# 02_SPEAKER_LED_STRIPS.net
KiCad netlist of a schematic drawn in Altium Designer
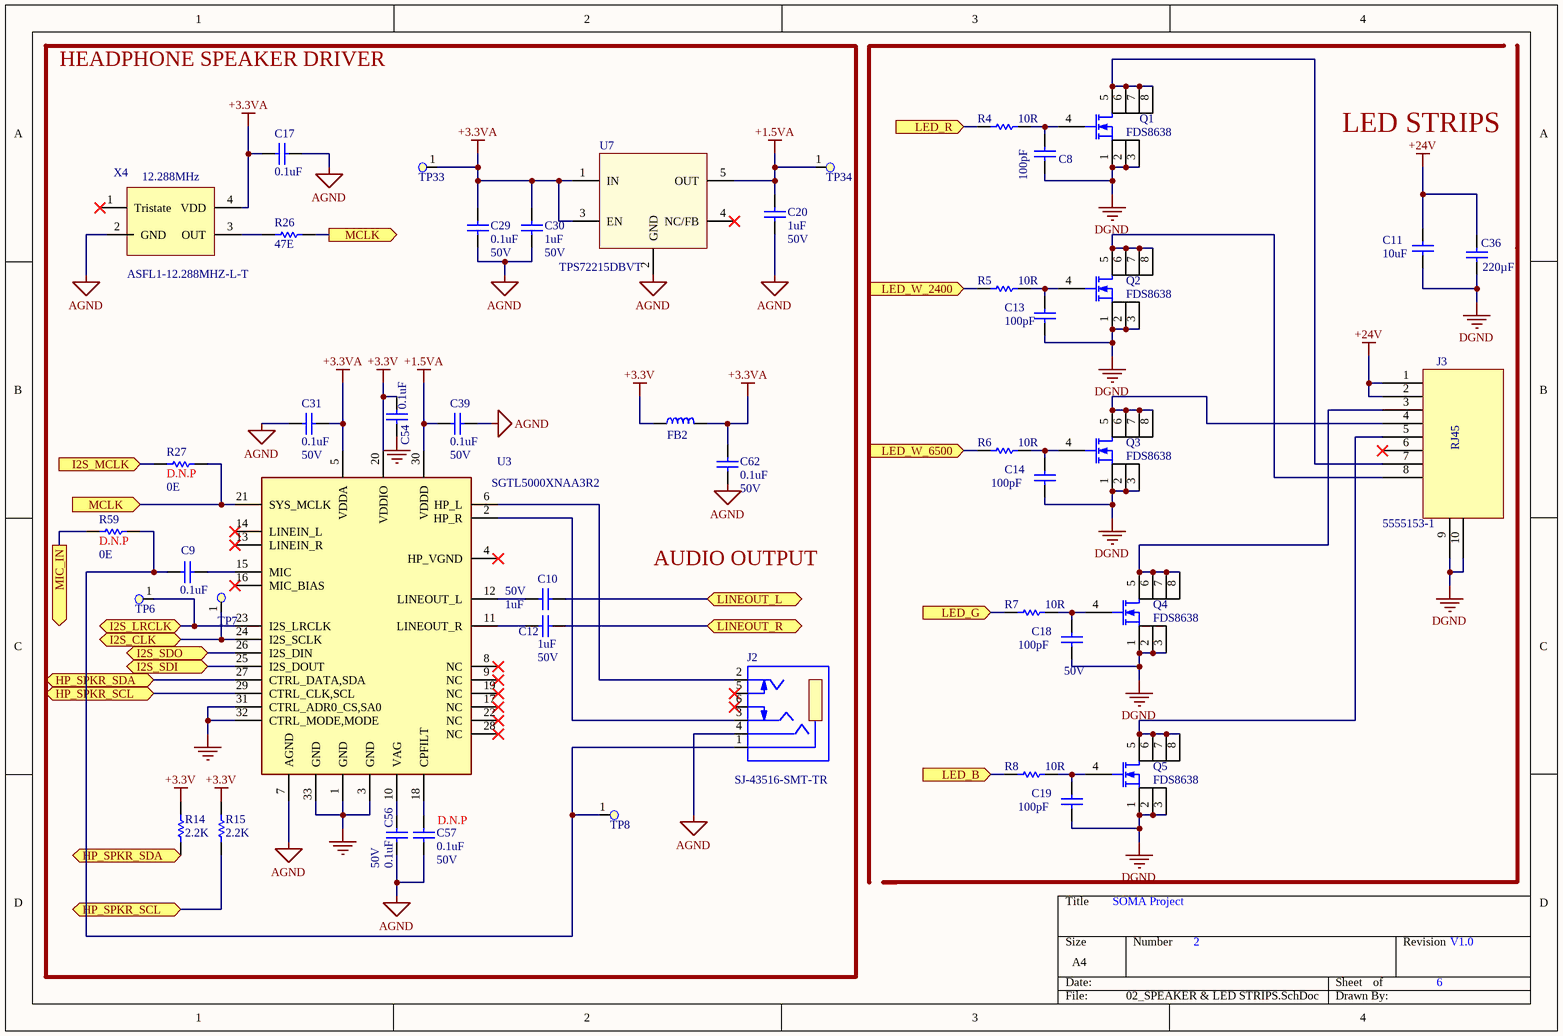
[diagram p0: 02_SPEAKER & LED STRIPS.SchDoc]

(export (version "E")
  (design (tool "Eeschema 10.0.6"))
  (components
    (comp (ref "C8")
      (value "100pF")
      (footprint "C0402")
      (description "100 pF ±5% 50V Ceramic Capacitor C0G, NP0 0402 (1005 Metric)")
      (fields (field (name "TOLERANCE") "±5%") (field (name "MANUFACTURER") "KEMET"))
      (libsource (lib "SOMA_15072021") (part "CAP CER 100PF 50V C0G/NP0 0402"))
    )
    (comp (ref "C9")
      (value "0.1uF")
      (footprint "C0603")
      (description "CAP CER 0.1UF 10V X7R 0603")
      (fields
        (field (name "MANUFACTURER") "Würth Elektronik")
        (field (name "DISTRIBUTOR PART NUMBER") "732-7939-1-ND")
      )
      (libsource (lib "SOMA_1") (part "CAP CER 0.1UF 10V X7R 0603"))
    )
    (comp (ref "C10")
      (value "1uF")
      (footprint "C0402")
      (description "1 µF ±10% 50V Ceramic Capacitor X5R 0402 (1005 Metric)")
      (fields
        (field (name "TOLERANCE") "±10%")
        (field (name "MANUFACTURER") "Taiyo Yuden")
        (field (name "RATING") "50V")
      )
      (libsource (lib "SOMA_15072021") (part "CAP CER 1UF 50V X5R 0402"))
    )
    (comp (ref "C11")
      (value "10uF")
      (footprint "C1206")
      (description "10µF ±20% 50V Ceramic Capacitor X5R 1206 (3216 Metric)")
      (fields (field (name "TOLERANCE") "±20%") (field (name "MANUFACTURER") "Samsung Electro-Mechanics"))
      (libsource (lib "SOMA_15072021") (part "CAP CER 10UF 50V X5R 1206"))
    )
    (comp (ref "C12")
      (value "1uF")
      (footprint "C0402")
      (description "1 µF ±10% 50V Ceramic Capacitor X5R 0402 (1005 Metric)")
      (fields
        (field (name "TOLERANCE") "±10%")
        (field (name "MANUFACTURER") "Taiyo Yuden")
        (field (name "RATING") "50V")
      )
      (libsource (lib "SOMA_15072021") (part "CAP CER 1UF 50V X5R 0402"))
    )
    (comp (ref "C13")
      (value "100pF")
      (footprint "C0402")
      (description "100 pF ±5% 50V Ceramic Capacitor C0G, NP0 0402 (1005 Metric)")
      (fields (field (name "TOLERANCE") "±5%") (field (name "MANUFACTURER") "KEMET"))
      (libsource (lib "SOMA_15072021") (part "CAP CER 100PF 50V C0G/NP0 0402"))
    )
    (comp (ref "C14")
      (value "100pF")
      (footprint "C0402")
      (description "100 pF ±5% 50V Ceramic Capacitor C0G, NP0 0402 (1005 Metric)")
      (fields (field (name "TOLERANCE") "±5%") (field (name "MANUFACTURER") "KEMET"))
      (libsource (lib "SOMA_15072021") (part "CAP CER 100PF 50V C0G/NP0 0402"))
    )
    (comp (ref "C17")
      (value "0.1uF")
      (footprint "C0603")
      (description "CAP CER 0.1UF 10V X7R 0603")
      (fields
        (field (name "MANUFACTURER") "Würth Elektronik")
        (field (name "DISTRIBUTOR PART NUMBER") "732-7939-1-ND")
      )
      (libsource (lib "SOMA_1") (part "CAP CER 0.1UF 10V X7R 0603"))
    )
    (comp (ref "C18")
      (value "100pF")
      (footprint "C0402")
      (description "100 pF ±5% 50V Ceramic Capacitor C0G, NP0 0402 (1005 Metric)")
      (fields
        (field (name "TOLERANCE") "±5%")
        (field (name "MANUFACTURER") "KEMET")
        (field (name "RATING") "50V")
      )
      (libsource (lib "SOMA_15072021") (part "CAP CER 100PF 50V C0G/NP0 0402"))
    )
    (comp (ref "C19")
      (value "100pF")
      (footprint "C0402")
      (description "100 pF ±5% 50V Ceramic Capacitor C0G, NP0 0402 (1005 Metric)")
      (fields (field (name "TOLERANCE") "±5%") (field (name "MANUFACTURER") "KEMET"))
      (libsource (lib "SOMA_15072021") (part "CAP CER 100PF 50V C0G/NP0 0402"))
    )
    (comp (ref "C20")
      (value "1uF")
      (footprint "C0603")
      (description "CAP CER 1UF 50V X5R 0603")
      (fields
        (field (name "MANUFACTURER") "Taiyo Yuden")
        (field (name "DISTRIBUTOR PART NUMBER") "587-2400-2-ND")
        (field (name "RATING") "50V")
      )
      (libsource (lib "SOMA_15072021") (part "CAP CER 1UF 50V X5R 0603"))
    )
    (comp (ref "C29")
      (value "0.1uF")
      (footprint "C0402")
      (description "CAP CER 0.1UF 50V X7R 0402")
      (fields
        (field (name "MANUFACTURER") "AVX")
        (field (name "MANUFACTURER PART NUMBER") "04025C104KAT2A")
        (field (name "RATING") "50V")
      )
      (libsource (lib "SOMA_15072021") (part "CAP CER 0.1UF 50V X7R 0402"))
    )
    (comp (ref "C30")
      (value "1uF")
      (footprint "C0603")
      (description "CAP CER 1UF 50V X5R 0603")
      (fields
        (field (name "MANUFACTURER") "Taiyo Yuden")
        (field (name "DISTRIBUTOR PART NUMBER") "587-2400-2-ND")
        (field (name "RATING") "50V")
      )
      (libsource (lib "SOMA_15072021") (part "CAP CER 1UF 50V X5R 0603"))
    )
    (comp (ref "C31")
      (value "0.1uF")
      (footprint "C0402")
      (description "CAP CER 0.1UF 50V X7R 0402")
      (fields
        (field (name "MANUFACTURER") "AVX")
        (field (name "MANUFACTURER PART NUMBER") "04025C104KAT2A")
        (field (name "RATING") "50V")
      )
      (libsource (lib "SOMA_15072021") (part "CAP CER 0.1UF 50V X7R 0402"))
    )
    (comp (ref "C36")
      (value "220µF")
      (footprint "C1206")
      (description "220µF ±20% 4V Ceramic Capacitor X5R 1206 (3216 Metric)")
      (fields
        (field (name "MANUFACTURER") "Murata Electronics")
        (field (name "DISTRIBUTOR PART NUMBER") "490-9774-2-ND")
      )
      (libsource (lib "SOMA_15072021") (part "CAP CER 220UF 4V X5R 1206"))
    )
    (comp (ref "C39")
      (value "0.1uF")
      (footprint "C0402")
      (description "CAP CER 0.1UF 50V X7R 0402")
      (fields
        (field (name "MANUFACTURER") "AVX")
        (field (name "MANUFACTURER PART NUMBER") "04025C104KAT2A")
        (field (name "RATING") "50V")
      )
      (libsource (lib "SOMA_15072021") (part "CAP CER 0.1UF 50V X7R 0402"))
    )
    (comp (ref "C54")
      (value "0.1uF")
      (footprint "C0603")
      (description "CAP CER 0.1UF 10V X7R 0603")
      (fields
        (field (name "MANUFACTURER") "Würth Elektronik")
        (field (name "DISTRIBUTOR PART NUMBER") "732-7939-1-ND")
      )
      (libsource (lib "SOMA_1") (part "CAP CER 0.1UF 10V X7R 0603"))
    )
    (comp (ref "C56")
      (value "0.1uF")
      (footprint "C0402")
      (description "CAP CER 0.1UF 50V X7R 0402")
      (fields
        (field (name "MANUFACTURER") "AVX")
        (field (name "MANUFACTURER PART NUMBER") "04025C104KAT2A")
        (field (name "RATING") "50V")
      )
      (libsource (lib "SOMA_15072021") (part "CAP CER 0.1UF 50V X7R 0402"))
    )
    (comp (ref "C57")
      (value "0.1uF")
      (footprint "C0402")
      (description "CAP CER 0.1UF 50V X7R 0402")
      (fields
        (field (name "MANUFACTURER") "AVX")
        (field (name "MANUFACTURER PART NUMBER") "04025C104KAT2A")
        (field (name "ASSEMBLY OPTION") "D.N.P")
        (field (name "RATING") "50V")
      )
      (libsource (lib "SOMA_15072021") (part "CAP CER 0.1UF 50V X7R 0402"))
    )
    (comp (ref "C62")
      (value "0.1uF")
      (footprint "C0402")
      (description "CAP CER 0.1UF 50V X7R 0402")
      (fields
        (field (name "MANUFACTURER") "AVX")
        (field (name "MANUFACTURER PART NUMBER") "04025C104KAT2A")
        (field (name "RATING") "50V")
      )
      (libsource (lib "SOMA_15072021") (part "CAP CER 0.1UF 50V X7R 0402"))
    )
    (comp (ref "FB2")
      (value "600 Ohms @ 100MHz")
      (footprint "FB0603")
      (description "FERRITE BEAD 600 OHM 0603 1LN")
      (fields (field (name "MANUFACTURER") "Murata") (field (name "DISTRIBUTOR PART NUMBER") "490-1014-2-ND"))
      (libsource (lib "SOMA_15072021") (part "FERRITE BEAD 600 OHM 0603 1LN"))
    )
    (comp (ref "J2")
      (value "CONN JACK 4COND 3.5MM SMD R/A")
      (footprint "CUI_SJ-43516-SMT-TR")
      (fields
        (field (name "MANUFACTURER") "CUI Devices")
        (field (name "MANUFACTURER PART NUMBER") "SJ-43516-SMT-TR")
        (field (name "DISTRIBUTOR PART NUMBER") "CP-43516SJCT-ND")
        (field (name "TOLERANCE") "NA")
      )
      (libsource (lib "SOMA_15072021") (part "CONN JACK 4COND 3.5MM SMD R/A"))
    )
    (comp (ref "J3")
      (value "5555153-1")
      (footprint "TE_55551531")
      (description "Jack Modular Connector 8p8c (RJ45, Ethernet) 90° Angle (Right) Shielded Cat3")
      (fields
        (field (name "DISTRIBUTOR PART NUMBER") "A31438-ND")
        (field (name "MANUFACTURER") "TE Connectivity AMP Connectors")
      )
      (libsource (lib "SOMA_15072021") (part "CONN MOD JACK 8P8C R/A SHIELDED"))
    )
    (comp (ref "Q1")
      (value "FDS8638")
      (footprint "SOIC127P600X175-8N")
      (description "N-Channel 40 V 18A (Ta) 2.5W (Ta) Surface Mount 8-SOIC")
      (fields
        (field (name "DISTRIBUTOR PART NUMBER") "FDS8638CT-ND")
        (field (name "MANUFACTURER") "ON Semiconductor")
      )
      (libsource (lib "SOMA_15072021") (part "MOSFET N-CH 40V 18A 8SOIC"))
    )
    (comp (ref "Q2")
      (value "FDS8638")
      (footprint "SOIC127P600X175-8N")
      (description "N-Channel 40 V 18A (Ta) 2.5W (Ta) Surface Mount 8-SOIC")
      (fields
        (field (name "DISTRIBUTOR PART NUMBER") "FDS8638CT-ND")
        (field (name "MANUFACTURER") "ON Semiconductor")
      )
      (libsource (lib "SOMA_15072021") (part "MOSFET N-CH 40V 18A 8SOIC"))
    )
    (comp (ref "Q3")
      (value "FDS8638")
      (footprint "SOIC127P600X175-8N")
      (description "N-Channel 40 V 18A (Ta) 2.5W (Ta) Surface Mount 8-SOIC")
      (fields
        (field (name "DISTRIBUTOR PART NUMBER") "FDS8638CT-ND")
        (field (name "MANUFACTURER") "ON Semiconductor")
      )
      (libsource (lib "SOMA_15072021") (part "MOSFET N-CH 40V 18A 8SOIC"))
    )
    (comp (ref "Q4")
      (value "FDS8638")
      (footprint "SOIC127P600X175-8N")
      (description "N-Channel 40 V 18A (Ta) 2.5W (Ta) Surface Mount 8-SOIC")
      (fields
        (field (name "DISTRIBUTOR PART NUMBER") "FDS8638CT-ND")
        (field (name "MANUFACTURER") "ON Semiconductor")
      )
      (libsource (lib "SOMA_15072021") (part "MOSFET N-CH 40V 18A 8SOIC"))
    )
    (comp (ref "Q5")
      (value "FDS8638")
      (footprint "SOIC127P600X175-8N")
      (description "N-Channel 40 V 18A (Ta) 2.5W (Ta) Surface Mount 8-SOIC")
      (fields
        (field (name "DISTRIBUTOR PART NUMBER") "FDS8638CT-ND")
        (field (name "MANUFACTURER") "ON Semiconductor")
      )
      (libsource (lib "SOMA_15072021") (part "MOSFET N-CH 40V 18A 8SOIC"))
    )
    (comp (ref "R4")
      (value "10R")
      (footprint "R0402")
      (description "10 Ohms ±5% 0.063W, 1/16W Chip Resistor 0402 (1005 Metric) Automotive AEC-Q200 Thick Film")
      (fields (field (name "TOLERANCE") "±5%") (field (name "MANUFACTURER") "Vishay Dale"))
      (libsource (lib "SOMA_15072021") (part "RES SMD 10 OHM 5% 1/16W 0402"))
    )
    (comp (ref "R5")
      (value "10R")
      (footprint "R0402")
      (description "10 Ohms ±5% 0.063W, 1/16W Chip Resistor 0402 (1005 Metric) Automotive AEC-Q200 Thick Film")
      (fields (field (name "TOLERANCE") "±5%") (field (name "MANUFACTURER") "Vishay Dale"))
      (libsource (lib "SOMA_15072021") (part "RES SMD 10 OHM 5% 1/16W 0402"))
    )
    (comp (ref "R6")
      (value "10R")
      (footprint "R0402")
      (description "10 Ohms ±5% 0.063W, 1/16W Chip Resistor 0402 (1005 Metric) Automotive AEC-Q200 Thick Film")
      (fields (field (name "TOLERANCE") "±5%") (field (name "MANUFACTURER") "Vishay Dale"))
      (libsource (lib "SOMA_15072021") (part "RES SMD 10 OHM 5% 1/16W 0402"))
    )
    (comp (ref "R7")
      (value "10R")
      (footprint "R0402")
      (description "10 Ohms ±5% 0.063W, 1/16W Chip Resistor 0402 (1005 Metric) Automotive AEC-Q200 Thick Film")
      (fields (field (name "TOLERANCE") "±5%") (field (name "MANUFACTURER") "Vishay Dale"))
      (libsource (lib "SOMA_15072021") (part "RES SMD 10 OHM 5% 1/16W 0402"))
    )
    (comp (ref "R8")
      (value "10R")
      (footprint "R0402")
      (description "10 Ohms ±5% 0.063W, 1/16W Chip Resistor 0402 (1005 Metric) Automotive AEC-Q200 Thick Film")
      (fields (field (name "TOLERANCE") "±5%") (field (name "MANUFACTURER") "Vishay Dale"))
      (libsource (lib "SOMA_15072021") (part "RES SMD 10 OHM 5% 1/16W 0402"))
    )
    (comp (ref "R14")
      (value "2.2K")
      (footprint "R0402")
      (description "2.2 kOhms ±1% 0.063W, 1/16W Chip Resistor 0402 (1005 Metric) Moisture Resistant Thick Film")
      (fields (field (name "TOLERANCE") "±1%") (field (name "MANUFACTURER") "YAGEO"))
      (libsource (lib "SOMA_15072021") (part "RES SMD 10 OHM 5% 1/16W 0402"))
    )
    (comp (ref "R15")
      (value "2.2K")
      (footprint "R0402")
      (description "2.2 kOhms ±1% 0.063W, 1/16W Chip Resistor 0402 (1005 Metric) Moisture Resistant Thick Film")
      (fields (field (name "TOLERANCE") "±1%") (field (name "MANUFACTURER") "YAGEO"))
      (libsource (lib "SOMA_15072021") (part "RES SMD 10 OHM 5% 1/16W 0402"))
    )
    (comp (ref "R26")
      (value "47E")
      (footprint "R0402")
      (description "RES SMD 47 OHM 5% 1/10W 0402")
      (fields (field (name "MANUFACTURER") "Panasonic") (field (name "DISTRIBUTOR PART NUMBER") "P47JTR-ND"))
      (libsource (lib "SOMA_15072021") (part "RES SMD 47 OHM 5% 1/10W 0402"))
    )
    (comp (ref "R27")
      (value "0E")
      (footprint "R0603")
      (description "RES SMD 0 OHM JUMPER 1/10W 0603")
      (fields
        (field (name "MANUFACTURER PART NUMBER") "RC0603JR-070RL")
        (field (name "MANUFACTURER") "Yageo")
        (field (name "ASSEMBLY OPTION") "D.N.P")
      )
      (libsource (lib "SOMA_15072021") (part "RES SMD 0 OHM JUMPER 1/10W 0603"))
    )
    (comp (ref "R59")
      (value "0E")
      (footprint "R0603")
      (description "RES SMD 0 OHM JUMPER 1/10W 0603")
      (fields
        (field (name "MANUFACTURER PART NUMBER") "RC0603JR-070RL")
        (field (name "MANUFACTURER") "Yageo")
        (field (name "ASSEMBLY OPTION") "D.N.P")
      )
      (libsource (lib "SOMA_15072021") (part "RES SMD 0 OHM JUMPER 1/10W 0603"))
    )
    (comp (ref "TP6")
      (value "Test Point,1.6mm Diameter,SMD")
      (footprint "TP_63C")
      (libsource (lib "SOMA_1") (part "Test Point,1.6mm Diameter,SMD"))
    )
    (comp (ref "TP7")
      (value "Test Point,1.6mm Diameter,SMD")
      (footprint "TP_63C")
      (libsource (lib "SOMA_1") (part "Test Point,1.6mm Diameter,SMD"))
    )
    (comp (ref "TP8")
      (value "Test Point,1.6mm Diameter,SMD")
      (footprint "TP_63C")
      (libsource (lib "SOMA_1") (part "Test Point,1.6mm Diameter,SMD"))
    )
    (comp (ref "TP33")
      (value "Test Point,1.6mm Diameter,SMD")
      (footprint "TP_63C")
      (libsource (lib "SOMA_1") (part "Test Point,1.6mm Diameter,SMD"))
    )
    (comp (ref "TP34")
      (value "Test Point,1.6mm Diameter,SMD")
      (footprint "TP_63C")
      (libsource (lib "SOMA_1") (part "Test Point,1.6mm Diameter,SMD"))
    )
    (comp (ref "U3")
      (value "SGTL5000XNAA3R2")
      (footprint "QFN50P500X500X100-33N")
      (description "Stereo Audio Interface - I²C, Serial, SPI™ 32-QFN-EP (5x5)")
      (fields
        (field (name "MANUFACTURER") "NXP USA Inc.")
        (field (name "DISTRIBUTOR PART NUMBER") "SGTL5000XNAA3R2CT-ND")
      )
      (libsource (lib "SOMA_15072021") (part "IC AUDIO CODEC STEREO 32-QFN"))
    )
    (comp (ref "U7")
      (value "TPS72215DBVT")
      (footprint "SOT95P280X145-5N")
      (description "IC REG LINEAR 1.5V 50MA SOT23-5")
      (fields
        (field (name "MANUFACTURER") "Texas Instruments")
        (field (name "DISTRIBUTOR PART NUMBER") "296-12521-1-ND")
      )
      (libsource (lib "SOMA_15072021") (part "IC REG LINEAR 1.5V 50MA SOT23-5"))
    )
    (comp (ref "X4")
      (value "12.288MHz")
      (footprint "XTAL500X320X130-4N")
      (description "XTAL OSC XO 12.2880MHZ HCMOS TTL")
      (fields
        (field (name "MANUFACTURER") "Abracon LLC")
        (field (name "DISTRIBUTOR PART NUMBER") "535-10810-1-ND")
        (field (name "MANUFACTURER PART NUMBER") "ASFL1-12.288MHZ-L-T")
      )
      (libsource (lib "SOMA_15072021") (part "XTAL OSC XO 12.2880MHZ HCMOS TTL"))
    )
  )
  (nets
    (net (code "1") (name "+1.5VA") (class "Default")
      (node (ref "C20") (pin "2") (pinfunction "2_2") (pintype "passive"))
      (node (ref "C39") (pin "2") (pinfunction "2_2") (pintype "passive"))
      (node (ref "TP34") (pin "1") (pinfunction "0_1") (pintype "passive"))
      (node (ref "U3") (pin "30") (pinfunction "VDDD_30") (pintype "passive"))
      (node (ref "U7") (pin "5") (pinfunction "OUT_5") (pintype "power_in"))
    )
    (net (code "2") (name "+3.3V") (class "Default")
      (node (ref "C54") (pin "1") (pinfunction "1_1") (pintype "passive"))
      (node (ref "FB2") (pin "2") (pinfunction "2_2") (pintype "passive"))
      (node (ref "R14") (pin "2") (pinfunction "2_2") (pintype "passive"))
      (node (ref "R15") (pin "2") (pinfunction "2_2") (pintype "passive"))
      (node (ref "U3") (pin "20") (pinfunction "VDDIO_20") (pintype "passive"))
    )
    (net (code "3") (name "+3.3VA") (class "Default")
      (node (ref "C17") (pin "2") (pinfunction "2_2") (pintype "passive"))
      (node (ref "C29") (pin "1") (pinfunction "1_1") (pintype "passive"))
      (node (ref "C30") (pin "2") (pinfunction "2_2") (pintype "passive"))
      (node (ref "C31") (pin "1") (pinfunction "1_1") (pintype "passive"))
      (node (ref "C62") (pin "2") (pinfunction "2_2") (pintype "passive"))
      (node (ref "FB2") (pin "1") (pinfunction "1_1") (pintype "passive"))
      (node (ref "TP33") (pin "1") (pinfunction "0_1") (pintype "passive"))
      (node (ref "U3") (pin "5") (pinfunction "VDDA_5") (pintype "passive"))
      (node (ref "U7") (pin "1") (pinfunction "IN_1") (pintype "power_in"))
      (node (ref "U7") (pin "3") (pinfunction "EN_3") (pintype "power_in"))
      (node (ref "X4") (pin "4") (pinfunction "VDD_4") (pintype "passive"))
    )
    (net (code "4") (name "+24V") (class "Default")
      (node (ref "C11") (pin "2") (pinfunction "2_2") (pintype "passive"))
      (node (ref "C36") (pin "2") (pinfunction "2_2") (pintype "passive"))
      (node (ref "J3") (pin "1") (pintype "passive"))
      (node (ref "J3") (pin "2") (pintype "passive"))
    )
    (net (code "5") (name "/HP_SPKR_SCL") (class "Default")
      (node (ref "R15") (pin "1") (pinfunction "1_1") (pintype "passive"))
      (node (ref "U3") (pin "29") (pinfunction "CTRL_CLK,SCL_29") (pintype "passive"))
    )
    (net (code "6") (name "/HP_SPKR_SDA") (class "Default")
      (node (ref "R14") (pin "1") (pinfunction "1_1") (pintype "passive"))
      (node (ref "U3") (pin "27") (pinfunction "CTRL_DATA,SDA_27") (pintype "passive"))
    )
    (net (code "7") (name "/I2S_CLK") (class "Default")
      (node (ref "TP7") (pin "1") (pinfunction "0_1") (pintype "passive"))
      (node (ref "U3") (pin "24") (pinfunction "I2S_SCLK_24") (pintype "passive"))
    )
    (net (code "8") (name "/I2S_LRCLK") (class "Default")
      (node (ref "TP6") (pin "1") (pinfunction "0_1") (pintype "passive"))
      (node (ref "U3") (pin "23") (pinfunction "I2S_LRCLK_23") (pintype "passive"))
    )
    (net (code "9") (name "/I2S_MCLK") (class "Default")
      (node (ref "R27") (pin "2") (pinfunction "2_2") (pintype "passive"))
    )
    (net (code "10") (name "/I2S_SDI") (class "Default")
      (node (ref "U3") (pin "25") (pinfunction "I2S_DOUT_25") (pintype "passive"))
    )
    (net (code "11") (name "/I2S_SDO") (class "Default")
      (node (ref "U3") (pin "26") (pinfunction "I2S_DIN_26") (pintype "passive"))
    )
    (net (code "12") (name "/LED_B") (class "Default")
      (node (ref "R8") (pin "1") (pinfunction "1_1") (pintype "passive"))
    )
    (net (code "13") (name "/LED_G") (class "Default")
      (node (ref "R7") (pin "1") (pinfunction "1_1") (pintype "passive"))
    )
    (net (code "14") (name "/LED_R") (class "Default")
      (node (ref "R4") (pin "1") (pinfunction "1_1") (pintype "passive"))
    )
    (net (code "15") (name "/LED_W_2400") (class "Default")
      (node (ref "R5") (pin "1") (pinfunction "1_1") (pintype "passive"))
    )
    (net (code "16") (name "/LED_W_6500") (class "Default")
      (node (ref "R6") (pin "1") (pinfunction "1_1") (pintype "passive"))
    )
    (net (code "17") (name "/LINEOUT_L") (class "Default")
      (node (ref "C10") (pin "2") (pinfunction "2_2") (pintype "passive"))
    )
    (net (code "18") (name "/LINEOUT_R") (class "Default")
      (node (ref "C12") (pin "2") (pinfunction "2_2") (pintype "passive"))
    )
    (net (code "19") (name "/MCLK") (class "Default")
      (node (ref "R26") (pin "2") (pinfunction "2_2") (pintype "passive"))
      (node (ref "R27") (pin "1") (pinfunction "1_1") (pintype "passive"))
      (node (ref "U3") (pin "21") (pinfunction "SYS_MCLK_21") (pintype "passive"))
    )
    (net (code "20") (name "/MIC_IN") (class "Default")
      (node (ref "R59") (pin "2") (pinfunction "2_2") (pintype "passive"))
    )
    (net (code "21") (name "AGND") (class "Default")
      (node (ref "C17") (pin "1") (pinfunction "1_1") (pintype "passive"))
      (node (ref "C20") (pin "1") (pinfunction "1_1") (pintype "passive"))
      (node (ref "C29") (pin "2") (pinfunction "2_2") (pintype "passive"))
      (node (ref "C30") (pin "1") (pinfunction "1_1") (pintype "passive"))
      (node (ref "C31") (pin "2") (pinfunction "2_2") (pintype "passive"))
      (node (ref "C39") (pin "1") (pinfunction "1_1") (pintype "passive"))
      (node (ref "C56") (pin "1") (pinfunction "1_1") (pintype "passive"))
      (node (ref "C57") (pin "1") (pinfunction "1_1") (pintype "passive"))
      (node (ref "C62") (pin "1") (pinfunction "1_1") (pintype "passive"))
      (node (ref "J2") (pin "4") (pinfunction "RING2_4") (pintype "passive"))
      (node (ref "U3") (pin "7") (pinfunction "AGND_7") (pintype "passive"))
      (node (ref "U7") (pin "2") (pinfunction "GND_2") (pintype "power_in"))
      (node (ref "X4") (pin "2") (pinfunction "GND_2") (pintype "power_in"))
    )
    (net (code "22") (name "DGND") (class "Default")
      (node (ref "C11") (pin "1") (pinfunction "1_1") (pintype "passive"))
      (node (ref "C13") (pin "1") (pinfunction "1_1") (pintype "passive"))
      (node (ref "C14") (pin "1") (pinfunction "1_1") (pintype "passive"))
      (node (ref "C18") (pin "1") (pinfunction "1_1") (pintype "passive"))
      (node (ref "C19") (pin "1") (pinfunction "1_1") (pintype "passive"))
      (node (ref "C36") (pin "1") (pinfunction "1_1") (pintype "passive"))
      (node (ref "C8") (pin "1") (pinfunction "1_1") (pintype "passive"))
      (node (ref "J3") (pin "10") (pinfunction "10_10") (pintype "passive"))
      (node (ref "J3") (pin "9") (pinfunction "9_9") (pintype "passive"))
      (node (ref "Q1") (pin "1") (pinfunction "1_1") (pintype "passive"))
      (node (ref "Q1") (pin "2") (pinfunction "2_2") (pintype "passive"))
      (node (ref "Q1") (pin "3") (pinfunction "3_3") (pintype "passive"))
      (node (ref "Q2") (pin "1") (pinfunction "1_1") (pintype "passive"))
      (node (ref "Q2") (pin "2") (pinfunction "2_2") (pintype "passive"))
      (node (ref "Q2") (pin "3") (pinfunction "3_3") (pintype "passive"))
      (node (ref "Q3") (pin "1") (pinfunction "1_1") (pintype "passive"))
      (node (ref "Q3") (pin "2") (pinfunction "2_2") (pintype "passive"))
      (node (ref "Q3") (pin "3") (pinfunction "3_3") (pintype "passive"))
      (node (ref "Q4") (pin "1") (pinfunction "1_1") (pintype "passive"))
      (node (ref "Q4") (pin "2") (pinfunction "2_2") (pintype "passive"))
      (node (ref "Q4") (pin "3") (pinfunction "3_3") (pintype "passive"))
      (node (ref "Q5") (pin "1") (pinfunction "1_1") (pintype "passive"))
      (node (ref "Q5") (pin "2") (pinfunction "2_2") (pintype "passive"))
      (node (ref "Q5") (pin "3") (pinfunction "3_3") (pintype "passive"))
    )
    (net (code "23") (name "GND") (class "Default")
      (node (ref "C54") (pin "2") (pinfunction "2_2") (pintype "passive"))
      (node (ref "U3") (pin "1") (pinfunction "GND_1") (pintype "passive"))
      (node (ref "U3") (pin "3") (pinfunction "GND_3") (pintype "passive"))
      (node (ref "U3") (pin "31") (pinfunction "CTRL_ADR0_CS,SA0_31") (pintype "passive"))
      (node (ref "U3") (pin "32") (pinfunction "CTRL_MODE,MODE_32") (pintype "passive"))
      (node (ref "U3") (pin "33") (pinfunction "GND_33") (pintype "passive"))
    )
    (net (code "24") (name "Net-(C8-Pad2)") (class "Default")
      (node (ref "C8") (pin "2") (pinfunction "2_2") (pintype "passive"))
      (node (ref "Q1") (pin "4") (pinfunction "4_4") (pintype "passive"))
      (node (ref "R4") (pin "2") (pinfunction "2_2") (pintype "passive"))
    )
    (net (code "25") (name "Net-(C13-Pad2)") (class "Default")
      (node (ref "C13") (pin "2") (pinfunction "2_2") (pintype "passive"))
      (node (ref "Q2") (pin "4") (pinfunction "4_4") (pintype "passive"))
      (node (ref "R5") (pin "2") (pinfunction "2_2") (pintype "passive"))
    )
    (net (code "26") (name "Net-(C14-Pad2)") (class "Default")
      (node (ref "C14") (pin "2") (pinfunction "2_2") (pintype "passive"))
      (node (ref "Q3") (pin "4") (pinfunction "4_4") (pintype "passive"))
      (node (ref "R6") (pin "2") (pinfunction "2_2") (pintype "passive"))
    )
    (net (code "27") (name "Net-(C18-Pad2)") (class "Default")
      (node (ref "C18") (pin "2") (pinfunction "2_2") (pintype "passive"))
      (node (ref "Q4") (pin "4") (pinfunction "4_4") (pintype "passive"))
      (node (ref "R7") (pin "2") (pinfunction "2_2") (pintype "passive"))
    )
    (net (code "28") (name "Net-(C19-Pad2)") (class "Default")
      (node (ref "C19") (pin "2") (pinfunction "2_2") (pintype "passive"))
      (node (ref "Q5") (pin "4") (pinfunction "4_4") (pintype "passive"))
      (node (ref "R8") (pin "2") (pinfunction "2_2") (pintype "passive"))
    )
    (net (code "29") (name "Net-(J2-RING1)") (class "Default")
      (node (ref "J2") (pin "3") (pinfunction "RING1_3") (pintype "passive"))
      (node (ref "U3") (pin "2") (pinfunction "HP_R_2") (pintype "passive"))
    )
    (net (code "30") (name "Net-(J2-SLEEVE)") (class "Default")
      (node (ref "C9") (pin "2") (pinfunction "2_2") (pintype "passive"))
      (node (ref "J2") (pin "1") (pinfunction "SLEEVE_1") (pintype "passive"))
      (node (ref "R59") (pin "1") (pinfunction "1_1") (pintype "passive"))
      (node (ref "TP8") (pin "1") (pinfunction "0_1") (pintype "passive"))
    )
    (net (code "31") (name "Net-(J2-TIP)") (class "Default")
      (node (ref "J2") (pin "2") (pinfunction "TIP_2") (pintype "passive"))
      (node (ref "U3") (pin "6") (pinfunction "HP_L_6") (pintype "passive"))
    )
    (net (code "32") (name "Net-(J3-Pad3)") (class "Default")
      (node (ref "J3") (pin "3") (pintype "passive"))
      (node (ref "Q4") (pin "5") (pinfunction "5_5") (pintype "passive"))
      (node (ref "Q4") (pin "6") (pinfunction "6_6") (pintype "passive"))
      (node (ref "Q4") (pin "7") (pinfunction "7_7") (pintype "passive"))
      (node (ref "Q4") (pin "8") (pinfunction "8_8") (pintype "passive"))
    )
    (net (code "33") (name "Net-(J3-Pad4)") (class "Default")
      (node (ref "J3") (pin "4") (pintype "passive"))
      (node (ref "Q3") (pin "5") (pinfunction "5_5") (pintype "passive"))
      (node (ref "Q3") (pin "6") (pinfunction "6_6") (pintype "passive"))
      (node (ref "Q3") (pin "7") (pinfunction "7_7") (pintype "passive"))
      (node (ref "Q3") (pin "8") (pinfunction "8_8") (pintype "passive"))
    )
    (net (code "34") (name "Net-(J3-Pad5)") (class "Default")
      (node (ref "J3") (pin "5") (pintype "passive"))
      (node (ref "Q5") (pin "5") (pinfunction "5_5") (pintype "passive"))
      (node (ref "Q5") (pin "6") (pinfunction "6_6") (pintype "passive"))
      (node (ref "Q5") (pin "7") (pinfunction "7_7") (pintype "passive"))
      (node (ref "Q5") (pin "8") (pinfunction "8_8") (pintype "passive"))
    )
    (net (code "35") (name "Net-(J3-Pad7)") (class "Default")
      (node (ref "J3") (pin "7") (pintype "passive"))
      (node (ref "Q1") (pin "5") (pinfunction "5_5") (pintype "passive"))
      (node (ref "Q1") (pin "6") (pinfunction "6_6") (pintype "passive"))
      (node (ref "Q1") (pin "7") (pinfunction "7_7") (pintype "passive"))
      (node (ref "Q1") (pin "8") (pinfunction "8_8") (pintype "passive"))
    )
    (net (code "36") (name "Net-(J3-Pad8)") (class "Default")
      (node (ref "J3") (pin "8") (pintype "passive"))
      (node (ref "Q2") (pin "5") (pinfunction "5_5") (pintype "passive"))
      (node (ref "Q2") (pin "6") (pinfunction "6_6") (pintype "passive"))
      (node (ref "Q2") (pin "7") (pinfunction "7_7") (pintype "passive"))
      (node (ref "Q2") (pin "8") (pinfunction "8_8") (pintype "passive"))
    )
    (net (code "37") (name "Net-(U3-CPFILT)") (class "Default")
      (node (ref "C57") (pin "2") (pinfunction "2_2") (pintype "passive"))
      (node (ref "U3") (pin "18") (pinfunction "CPFILT_18") (pintype "passive"))
    )
    (net (code "38") (name "Net-(U3-LINEOUT_L)") (class "Default")
      (node (ref "C10") (pin "1") (pinfunction "1_1") (pintype "passive"))
      (node (ref "U3") (pin "12") (pinfunction "LINEOUT_L_12") (pintype "passive"))
    )
    (net (code "39") (name "Net-(U3-LINEOUT_R)") (class "Default")
      (node (ref "C12") (pin "1") (pinfunction "1_1") (pintype "passive"))
      (node (ref "U3") (pin "11") (pinfunction "LINEOUT_R_11") (pintype "passive"))
    )
    (net (code "40") (name "Net-(U3-MIC)") (class "Default")
      (node (ref "C9") (pin "1") (pinfunction "1_1") (pintype "passive"))
      (node (ref "U3") (pin "15") (pinfunction "MIC_15") (pintype "passive"))
    )
    (net (code "41") (name "Net-(U3-VAG)") (class "Default")
      (node (ref "C56") (pin "2") (pinfunction "2_2") (pintype "passive"))
      (node (ref "U3") (pin "10") (pinfunction "VAG_10") (pintype "passive"))
    )
    (net (code "42") (name "Net-(X4-OUT)") (class "Default")
      (node (ref "R26") (pin "1") (pinfunction "1_1") (pintype "passive"))
      (node (ref "X4") (pin "3") (pinfunction "OUT_3") (pintype "passive"))
    )
    (net (code "43") (name "unconnected-(J2-RING_SWITCH-Pad6)") (class "Default")
      (node (ref "J2") (pin "6") (pinfunction "RING_SWITCH_6") (pintype "passive+no_connect"))
    )
    (net (code "44") (name "unconnected-(J2-TIP_SWITCH-Pad5)") (class "Default")
      (node (ref "J2") (pin "5") (pinfunction "TIP_SWITCH_5") (pintype "passive+no_connect"))
    )
    (net (code "45") (name "unconnected-(J3-Pad6)") (class "Default")
      (node (ref "J3") (pin "6") (pintype "passive+no_connect"))
    )
    (net (code "46") (name "unconnected-(U3-HP_VGND-Pad4)") (class "Default")
      (node (ref "U3") (pin "4") (pinfunction "HP_VGND_4") (pintype "passive+no_connect"))
    )
    (net (code "47") (name "unconnected-(U3-LINEIN_L-Pad14)") (class "Default")
      (node (ref "U3") (pin "14") (pinfunction "LINEIN_L_14") (pintype "passive+no_connect"))
    )
    (net (code "48") (name "unconnected-(U3-LINEIN_R-Pad13)") (class "Default")
      (node (ref "U3") (pin "13") (pinfunction "LINEIN_R_13") (pintype "passive+no_connect"))
    )
    (net (code "49") (name "unconnected-(U3-MIC_BIAS-Pad16)") (class "Default")
      (node (ref "U3") (pin "16") (pinfunction "MIC_BIAS_16") (pintype "passive+no_connect"))
    )
    (net (code "50") (name "unconnected-(U3-NC-Pad8)") (class "Default")
      (node (ref "U3") (pin "8") (pinfunction "NC_8") (pintype "passive+no_connect"))
    )
    (net (code "51") (name "unconnected-(U3-NC-Pad9)") (class "Default")
      (node (ref "U3") (pin "9") (pinfunction "NC_9") (pintype "passive+no_connect"))
    )
    (net (code "52") (name "unconnected-(U3-NC-Pad17)") (class "Default")
      (node (ref "U3") (pin "17") (pinfunction "NC_17") (pintype "passive+no_connect"))
    )
    (net (code "53") (name "unconnected-(U3-NC-Pad19)") (class "Default")
      (node (ref "U3") (pin "19") (pinfunction "NC_19") (pintype "passive+no_connect"))
    )
    (net (code "54") (name "unconnected-(U3-NC-Pad22)") (class "Default")
      (node (ref "U3") (pin "22") (pinfunction "NC_22") (pintype "passive+no_connect"))
    )
    (net (code "55") (name "unconnected-(U3-NC-Pad28)") (class "Default")
      (node (ref "U3") (pin "28") (pinfunction "NC_28") (pintype "passive+no_connect"))
    )
    (net (code "56") (name "unconnected-(U7-NC{slash}FB-Pad4)") (class "Default")
      (node (ref "U7") (pin "4") (pinfunction "NC/FB_4") (pintype "power_in+no_connect"))
    )
    (net (code "57") (name "unconnected-(X4-Tristate-Pad1)") (class "Default")
      (node (ref "X4") (pin "1") (pinfunction "Tristate_1") (pintype "passive+no_connect"))
    )
  )
)
